# memory.net
KiCad netlist of a schematic drawn in Altium Designer
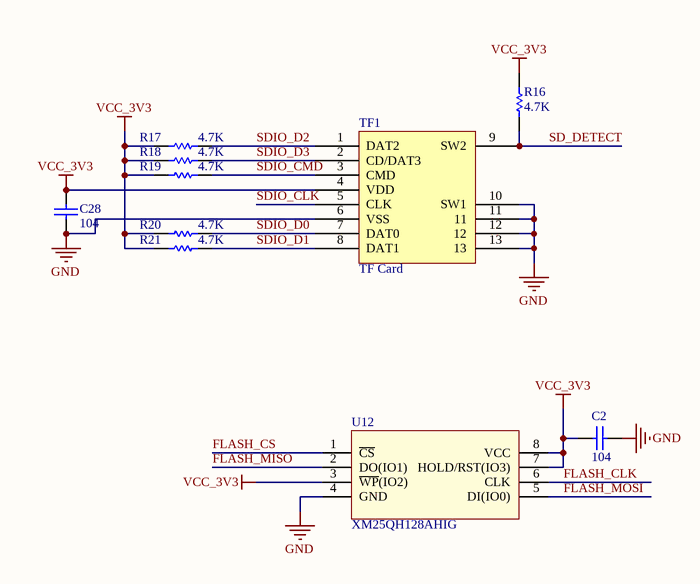
[diagram p0: memory.SchDoc]

(export (version "E")
  (design (tool "Eeschema 10.0.6"))
  (components
    (comp (ref "C2")
      (value "104")
      (footprint "ABmain:C 0603")
      (description "Capacitor")
      (libsource (lib "Miscellaneous Devices") (part "Cap"))
    )
    (comp (ref "C28")
      (value "104")
      (footprint "C 0603")
      (description "Capacitor")
      (libsource (lib "Miscellaneous Devices") (part "Cap"))
    )
    (comp (ref "R16") (value "4.7K") (footprint "R 0603") (libsource (lib "Sheet") (part "RES")))
    (comp (ref "R17") (value "4.7K") (footprint "R 0603") (libsource (lib "Sheet") (part "RES")))
    (comp (ref "R18") (value "4.7K") (footprint "R 0603") (libsource (lib "Sheet") (part "RES")))
    (comp (ref "R19") (value "4.7K") (footprint "R 0603") (libsource (lib "Sheet") (part "RES")))
    (comp (ref "R20") (value "4.7K") (footprint "R 0603") (libsource (lib "Sheet") (part "RES")))
    (comp (ref "R21") (value "4.7K") (footprint "R 0603") (libsource (lib "Sheet") (part "RES")))
    (comp (ref "TF1")
      (value "TF Card")
      (footprint "TF-Card")
      (libsource (lib "Bison-Board") (part "TF Card"))
    )
    (comp (ref "U12")
      (value "XM25QH128AHIG")
      (footprint "SOIC-8")
      (libsource (lib "Bison-Board") (part "W25Q128"))
    )
  )
  (nets
    (net (code "1") (name "/FLASH_CLK") (class "Default")
      (node (ref "U12") (pin "6") (pinfunction "CLK_6") (pintype "passive"))
    )
    (net (code "2") (name "/FLASH_CS") (class "Default")
      (node (ref "U12") (pin "1") (pinfunction "~{CS}_1") (pintype "passive"))
    )
    (net (code "3") (name "/FLASH_MISO") (class "Default")
      (node (ref "U12") (pin "2") (pinfunction "DO(IO1)_2") (pintype "passive"))
    )
    (net (code "4") (name "/FLASH_MOSI") (class "Default")
      (node (ref "U12") (pin "5") (pinfunction "DI(IO0)_5") (pintype "passive"))
    )
    (net (code "5") (name "/SDIO_CLK") (class "Default")
      (node (ref "TF1") (pin "5") (pinfunction "CLK_5") (pintype "passive"))
    )
    (net (code "6") (name "/SDIO_CMD") (class "Default")
      (node (ref "R19") (pin "2") (pinfunction "2_2") (pintype "passive"))
      (node (ref "TF1") (pin "3") (pinfunction "CMD_3") (pintype "passive"))
    )
    (net (code "7") (name "/SDIO_D0") (class "Default")
      (node (ref "R20") (pin "2") (pinfunction "2_2") (pintype "passive"))
      (node (ref "TF1") (pin "7") (pinfunction "DAT0_7") (pintype "passive"))
    )
    (net (code "8") (name "/SDIO_D1") (class "Default")
      (node (ref "R21") (pin "2") (pinfunction "2_2") (pintype "passive"))
      (node (ref "TF1") (pin "8") (pinfunction "DAT1_8") (pintype "passive"))
    )
    (net (code "9") (name "/SDIO_D2") (class "Default")
      (node (ref "R17") (pin "2") (pinfunction "2_2") (pintype "passive"))
      (node (ref "TF1") (pin "1") (pinfunction "DAT2_1") (pintype "passive"))
    )
    (net (code "10") (name "/SDIO_D3") (class "Default")
      (node (ref "R18") (pin "2") (pinfunction "2_2") (pintype "passive"))
      (node (ref "TF1") (pin "2") (pinfunction "CD/DAT3_2") (pintype "passive"))
    )
    (net (code "11") (name "/SD_DETECT") (class "Default")
      (node (ref "R16") (pin "1") (pinfunction "1_1") (pintype "passive"))
      (node (ref "TF1") (pin "9") (pinfunction "SW2_9") (pintype "passive"))
    )
    (net (code "12") (name "GND") (class "Default")
      (node (ref "C2") (pin "2") (pinfunction "2_2") (pintype "passive"))
      (node (ref "C28") (pin "2") (pinfunction "2_2") (pintype "passive"))
      (node (ref "TF1") (pin "10") (pinfunction "SW1_10") (pintype "passive"))
      (node (ref "TF1") (pin "11") (pinfunction "11_11") (pintype "passive"))
      (node (ref "TF1") (pin "12") (pinfunction "12_12") (pintype "passive"))
      (node (ref "TF1") (pin "13") (pinfunction "13_13") (pintype "passive"))
      (node (ref "TF1") (pin "6") (pinfunction "VSS_6") (pintype "passive"))
      (node (ref "U12") (pin "4") (pinfunction "GND_4") (pintype "passive"))
    )
    (net (code "13") (name "VCC_3V3") (class "Default")
      (node (ref "C2") (pin "1") (pinfunction "1_1") (pintype "passive"))
      (node (ref "C28") (pin "1") (pinfunction "1_1") (pintype "passive"))
      (node (ref "R16") (pin "2") (pinfunction "2_2") (pintype "passive"))
      (node (ref "R17") (pin "1") (pinfunction "1_1") (pintype "passive"))
      (node (ref "R18") (pin "1") (pinfunction "1_1") (pintype "passive"))
      (node (ref "R19") (pin "1") (pinfunction "1_1") (pintype "passive"))
      (node (ref "R20") (pin "1") (pinfunction "1_1") (pintype "passive"))
      (node (ref "R21") (pin "1") (pinfunction "1_1") (pintype "passive"))
      (node (ref "TF1") (pin "4") (pinfunction "VDD_4") (pintype "passive"))
      (node (ref "U12") (pin "3") (pinfunction "~{WP}(IO2)_3") (pintype "passive"))
      (node (ref "U12") (pin "7") (pinfunction "HOLD/RST(IO3)_7") (pintype "passive"))
      (node (ref "U12") (pin "8") (pinfunction "VCC_8") (pintype "passive"))
    )
  )
)
